# MikroBus-Connecteur.net
KiCad netlist of a schematic drawn in Altium Designer
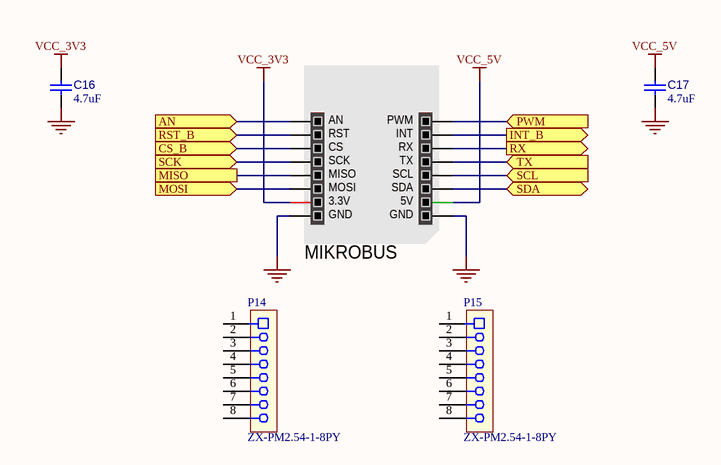
[diagram p0: MikroBus-Connecteur.SchDoc]

(export (version "E")
  (design (tool "Eeschema 10.0.6"))
  (components
    (comp (ref "C16")
      (value "4.7uF")
      (footprint "C_2012[0805]")
      (description "Capacitor type 1")
      (fields (field (name "TOLERANCE") "10%") (field (name "Comment") "Cap 4.7uF 0805"))
      (libsource (lib "TEP_243-Altium_DBLib") (part "capacitor"))
    )
    (comp (ref "C17")
      (value "4.7uF")
      (footprint "C_2012[0805]")
      (description "Capacitor type 1")
      (fields (field (name "TOLERANCE") "10%") (field (name "Comment") "Cap 4.7uF 0805"))
      (libsource (lib "TEP_243-Altium_DBLib") (part "capacitor"))
    )
    (comp (ref "MIKROBUS")
      (value "MIKROBUS HOST CONN.")
      (footprint "MIKROBUS HOST CONN. TH")
      (description "mikroBUS Host Socket")
      (libsource (lib "mikroBUS_socket_standard") (part "MIKROBUS-HOST-CONN"))
    )
    (comp (ref "P14")
      (value "ZX-PM2.54-1-8PY")
      (footprint "CONN_SKT_01X08_100MIL")
      (description "CONN SOCKET 8pos 100mils")
      (libsource (lib "TEP_243-AltiumLIB-Conn-TP-MH") (part "CONN-100MIL-SKT-01X08"))
    )
    (comp (ref "P15")
      (value "ZX-PM2.54-1-8PY")
      (footprint "CONN_SKT_01X08_100MIL")
      (description "CONN SOCKET 8pos 100mils")
      (libsource (lib "TEP_243-AltiumLIB-Conn-TP-MH") (part "CONN-100MIL-SKT-01X08"))
    )
  )
  (nets
    (net (code "1") (name "/AN") (class "Default")
      (node (ref "MIKROBUS") (pin "1") (pinfunction "AN_1") (pintype "passive"))
    )
    (net (code "2") (name "/CS_B") (class "Default")
      (node (ref "MIKROBUS") (pin "3") (pinfunction "CS_3") (pintype "passive"))
    )
    (net (code "3") (name "/INT_B") (class "Default")
      (node (ref "MIKROBUS") (pin "15") (pinfunction "INT_15") (pintype "passive"))
    )
    (net (code "4") (name "/MISO") (class "Default")
      (node (ref "MIKROBUS") (pin "5") (pinfunction "MISO_5") (pintype "passive"))
    )
    (net (code "5") (name "/MOSI") (class "Default")
      (node (ref "MIKROBUS") (pin "6") (pinfunction "MOSI_6") (pintype "passive"))
    )
    (net (code "6") (name "/PWM") (class "Default")
      (node (ref "MIKROBUS") (pin "16") (pinfunction "PWM_16") (pintype "passive"))
    )
    (net (code "7") (name "/RST_B") (class "Default")
      (node (ref "MIKROBUS") (pin "2") (pinfunction "RST_2") (pintype "passive"))
    )
    (net (code "8") (name "/RX") (class "Default")
      (node (ref "MIKROBUS") (pin "14") (pinfunction "RX_14") (pintype "passive"))
    )
    (net (code "9") (name "/SCK") (class "Default")
      (node (ref "MIKROBUS") (pin "4") (pinfunction "SCK_4") (pintype "passive"))
    )
    (net (code "10") (name "/SCL") (class "Default")
      (node (ref "MIKROBUS") (pin "12") (pinfunction "SCL_12") (pintype "passive"))
    )
    (net (code "11") (name "/SDA") (class "Default")
      (node (ref "MIKROBUS") (pin "11") (pinfunction "SDA_11") (pintype "passive"))
    )
    (net (code "12") (name "/TX") (class "Default")
      (node (ref "MIKROBUS") (pin "13") (pinfunction "TX_13") (pintype "passive"))
    )
    (net (code "13") (name "GND") (class "Default")
      (node (ref "C16") (pin "1") (pinfunction "1_1") (pintype "passive"))
      (node (ref "C17") (pin "1") (pinfunction "1_1") (pintype "passive"))
      (node (ref "MIKROBUS") (pin "8") (pinfunction "GND_8") (pintype "passive"))
      (node (ref "MIKROBUS") (pin "9") (pinfunction "GND_9") (pintype "passive"))
    )
    (net (code "14") (name "VCC_3V3") (class "Default")
      (node (ref "C16") (pin "2") (pinfunction "2_2") (pintype "passive"))
      (node (ref "MIKROBUS") (pin "7") (pinfunction "3.3V_7") (pintype "passive"))
    )
    (net (code "15") (name "VCC_5V") (class "Default")
      (node (ref "C17") (pin "2") (pinfunction "2_2") (pintype "passive"))
      (node (ref "MIKROBUS") (pin "10") (pinfunction "5V_10") (pintype "passive"))
    )
    (net (code "16") (name "unconnected-(P14-Pad1)") (class "Default")
      (node (ref "P14") (pin "1") (pinfunction "1_1") (pintype "passive"))
    )
    (net (code "17") (name "unconnected-(P14-Pad2)") (class "Default")
      (node (ref "P14") (pin "2") (pinfunction "2_2") (pintype "passive"))
    )
    (net (code "18") (name "unconnected-(P14-Pad3)") (class "Default")
      (node (ref "P14") (pin "3") (pinfunction "3_3") (pintype "passive"))
    )
    (net (code "19") (name "unconnected-(P14-Pad4)") (class "Default")
      (node (ref "P14") (pin "4") (pinfunction "4_4") (pintype "passive"))
    )
    (net (code "20") (name "unconnected-(P14-Pad5)") (class "Default")
      (node (ref "P14") (pin "5") (pinfunction "5_5") (pintype "passive"))
    )
    (net (code "21") (name "unconnected-(P14-Pad6)") (class "Default")
      (node (ref "P14") (pin "6") (pinfunction "6_6") (pintype "passive"))
    )
    (net (code "22") (name "unconnected-(P14-Pad7)") (class "Default")
      (node (ref "P14") (pin "7") (pinfunction "7_7") (pintype "passive"))
    )
    (net (code "23") (name "unconnected-(P14-Pad8)") (class "Default")
      (node (ref "P14") (pin "8") (pinfunction "8_8") (pintype "passive"))
    )
    (net (code "24") (name "unconnected-(P15-Pad1)") (class "Default")
      (node (ref "P15") (pin "1") (pinfunction "1_1") (pintype "passive"))
    )
    (net (code "25") (name "unconnected-(P15-Pad2)") (class "Default")
      (node (ref "P15") (pin "2") (pinfunction "2_2") (pintype "passive"))
    )
    (net (code "26") (name "unconnected-(P15-Pad3)") (class "Default")
      (node (ref "P15") (pin "3") (pinfunction "3_3") (pintype "passive"))
    )
    (net (code "27") (name "unconnected-(P15-Pad4)") (class "Default")
      (node (ref "P15") (pin "4") (pinfunction "4_4") (pintype "passive"))
    )
    (net (code "28") (name "unconnected-(P15-Pad5)") (class "Default")
      (node (ref "P15") (pin "5") (pinfunction "5_5") (pintype "passive"))
    )
    (net (code "29") (name "unconnected-(P15-Pad6)") (class "Default")
      (node (ref "P15") (pin "6") (pinfunction "6_6") (pintype "passive"))
    )
    (net (code "30") (name "unconnected-(P15-Pad7)") (class "Default")
      (node (ref "P15") (pin "7") (pinfunction "7_7") (pintype "passive"))
    )
    (net (code "31") (name "unconnected-(P15-Pad8)") (class "Default")
      (node (ref "P15") (pin "8") (pinfunction "8_8") (pintype "passive"))
    )
  )
)
